# 05_MSM8916_CONTROL.net
KiCad netlist of a schematic drawn in Altium Designer
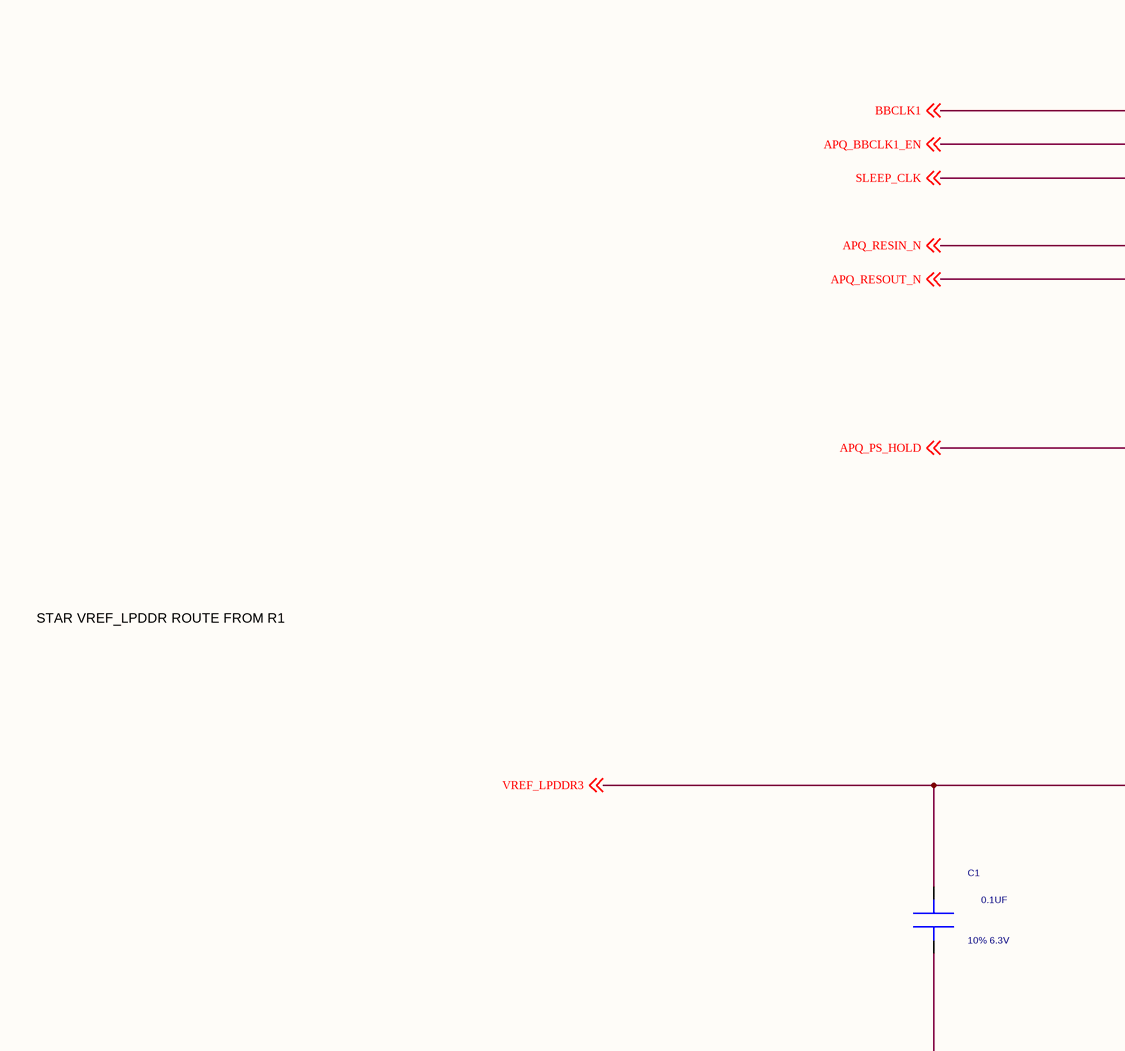
[diagram p0: 05 MSM8916_CONTROL.SchDoc, top left]
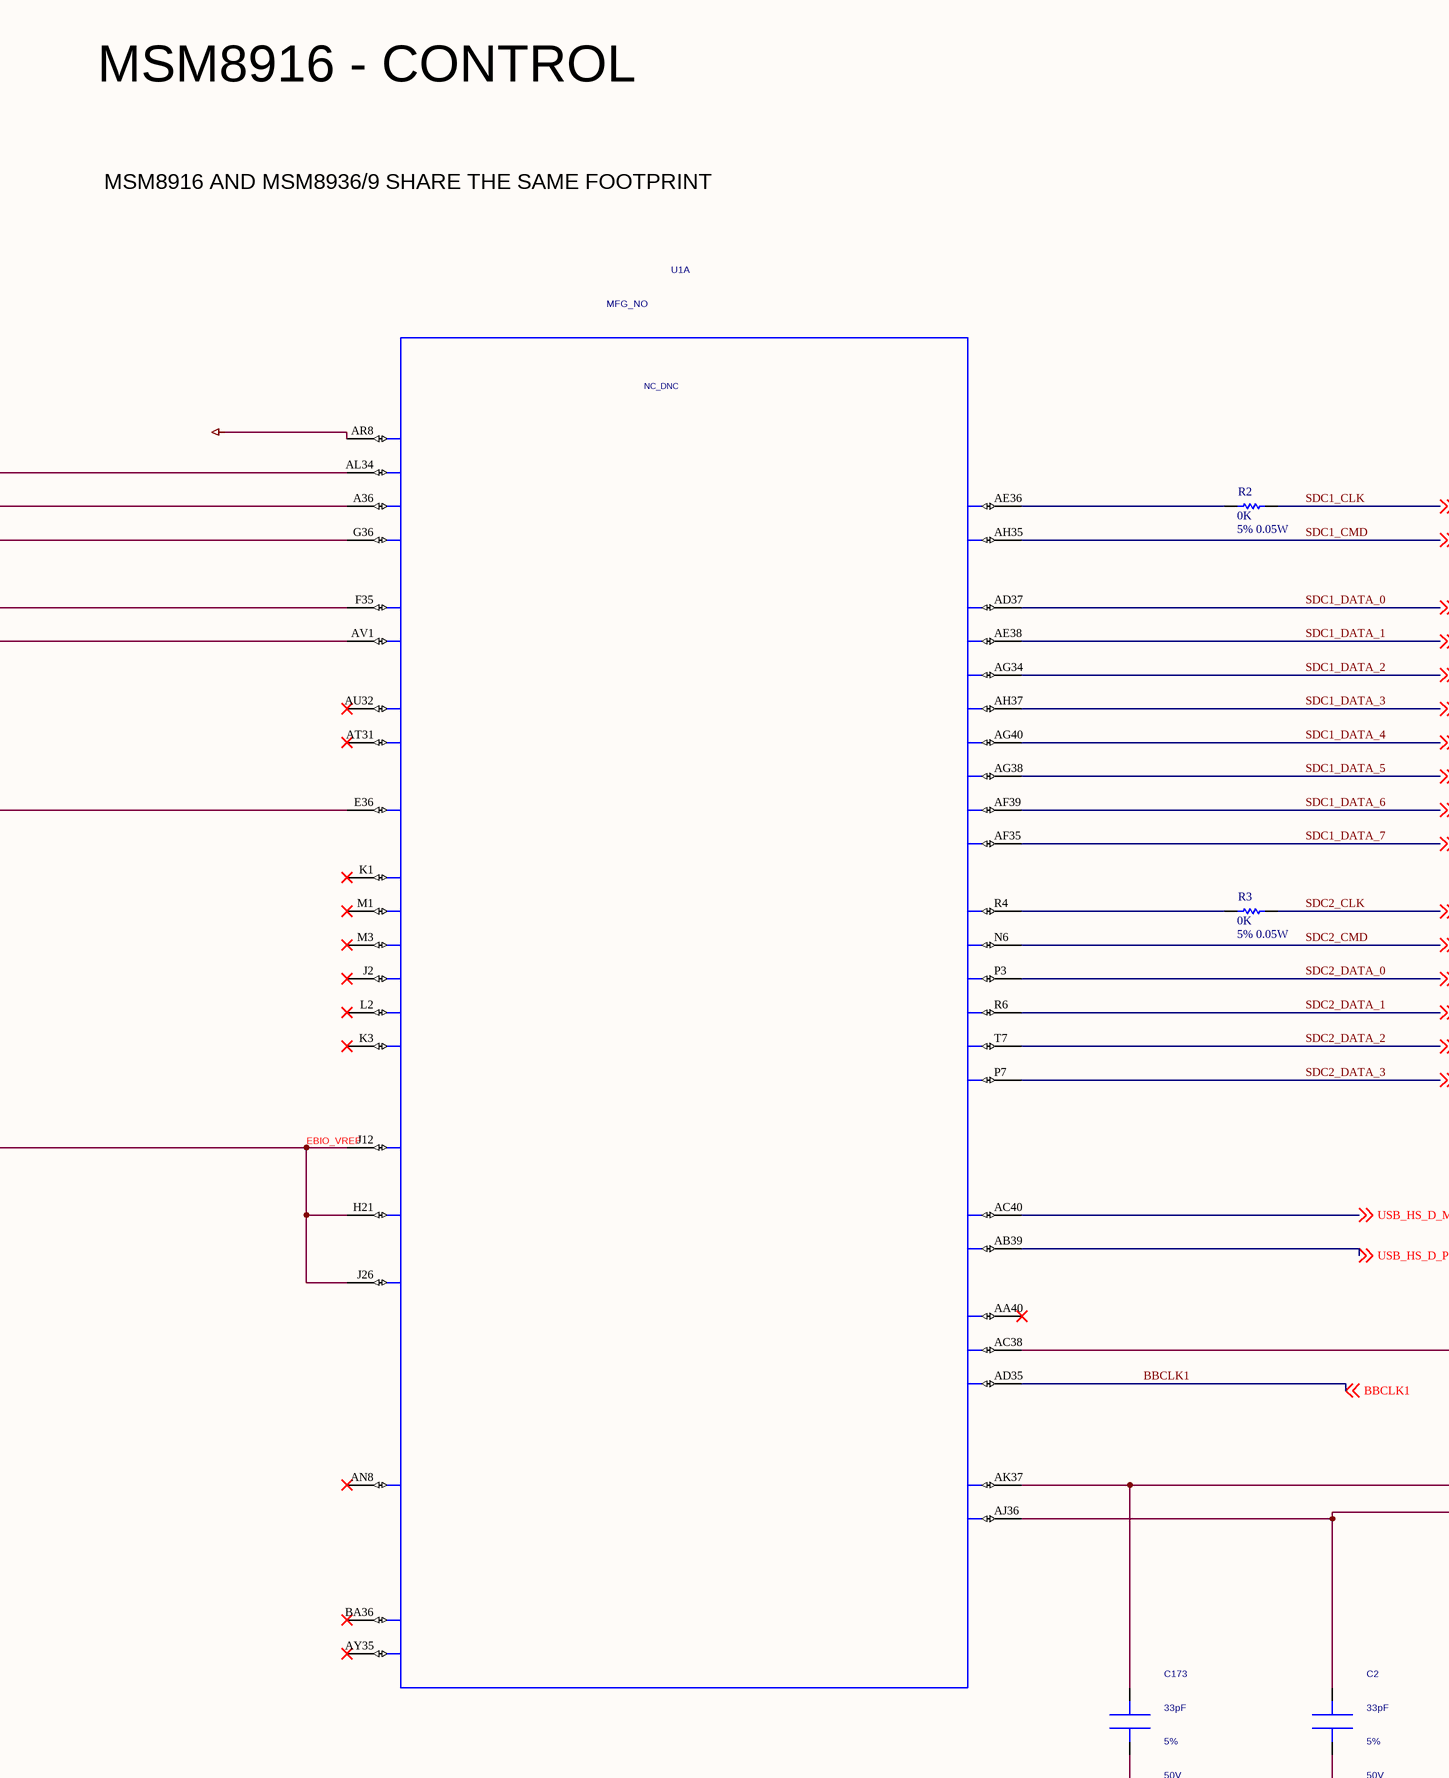
[diagram p1: 05 MSM8916_CONTROL.SchDoc, top middle]
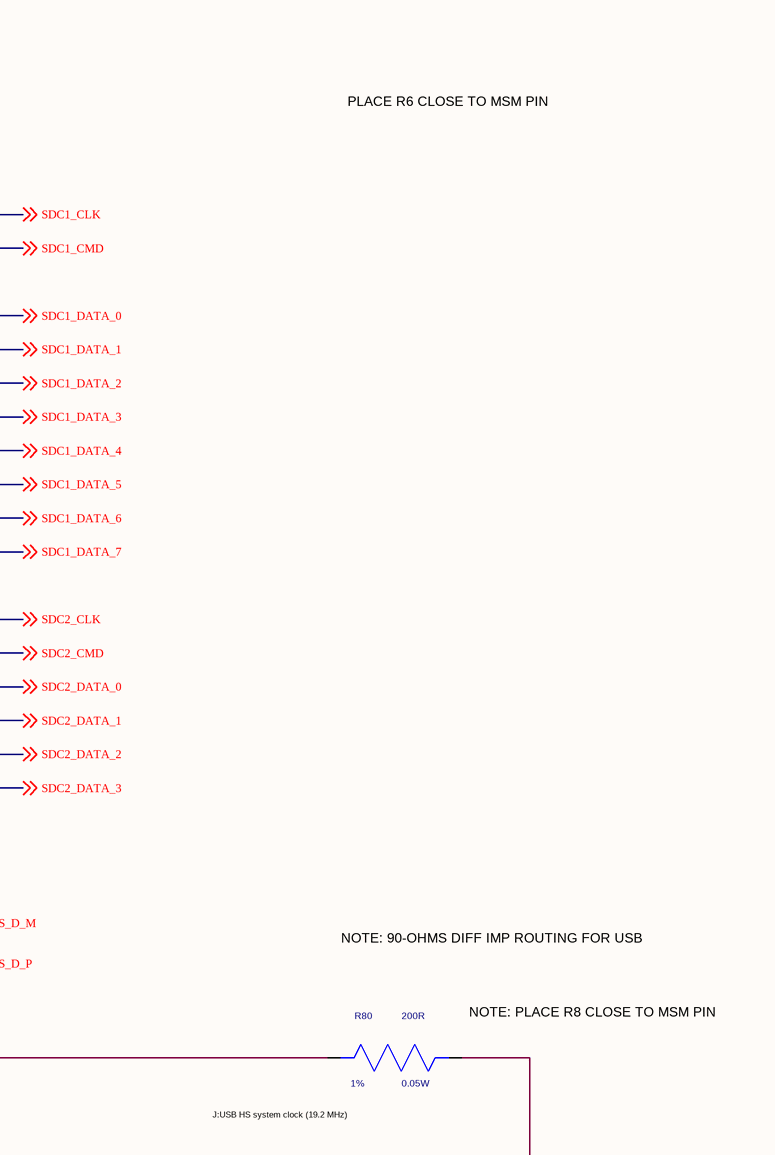
[diagram p2: 05 MSM8916_CONTROL.SchDoc, top right]
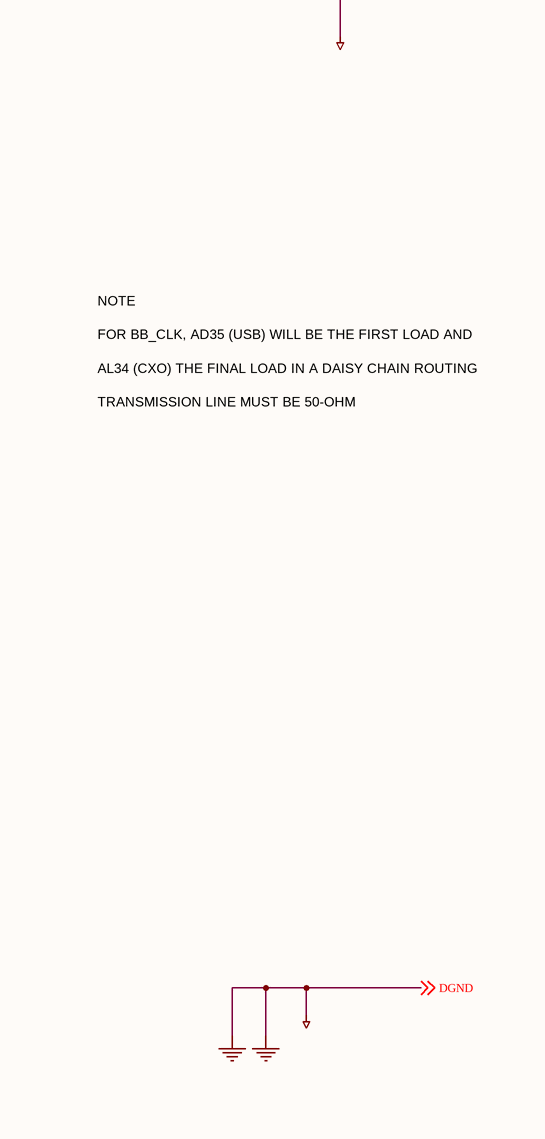
[diagram p3: 05 MSM8916_CONTROL.SchDoc, bottom left]
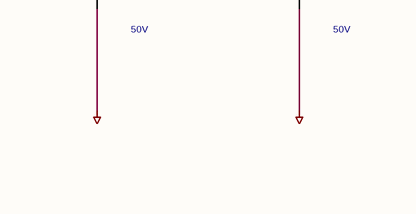
[diagram p4: 05 MSM8916_CONTROL.SchDoc, bottom middle]
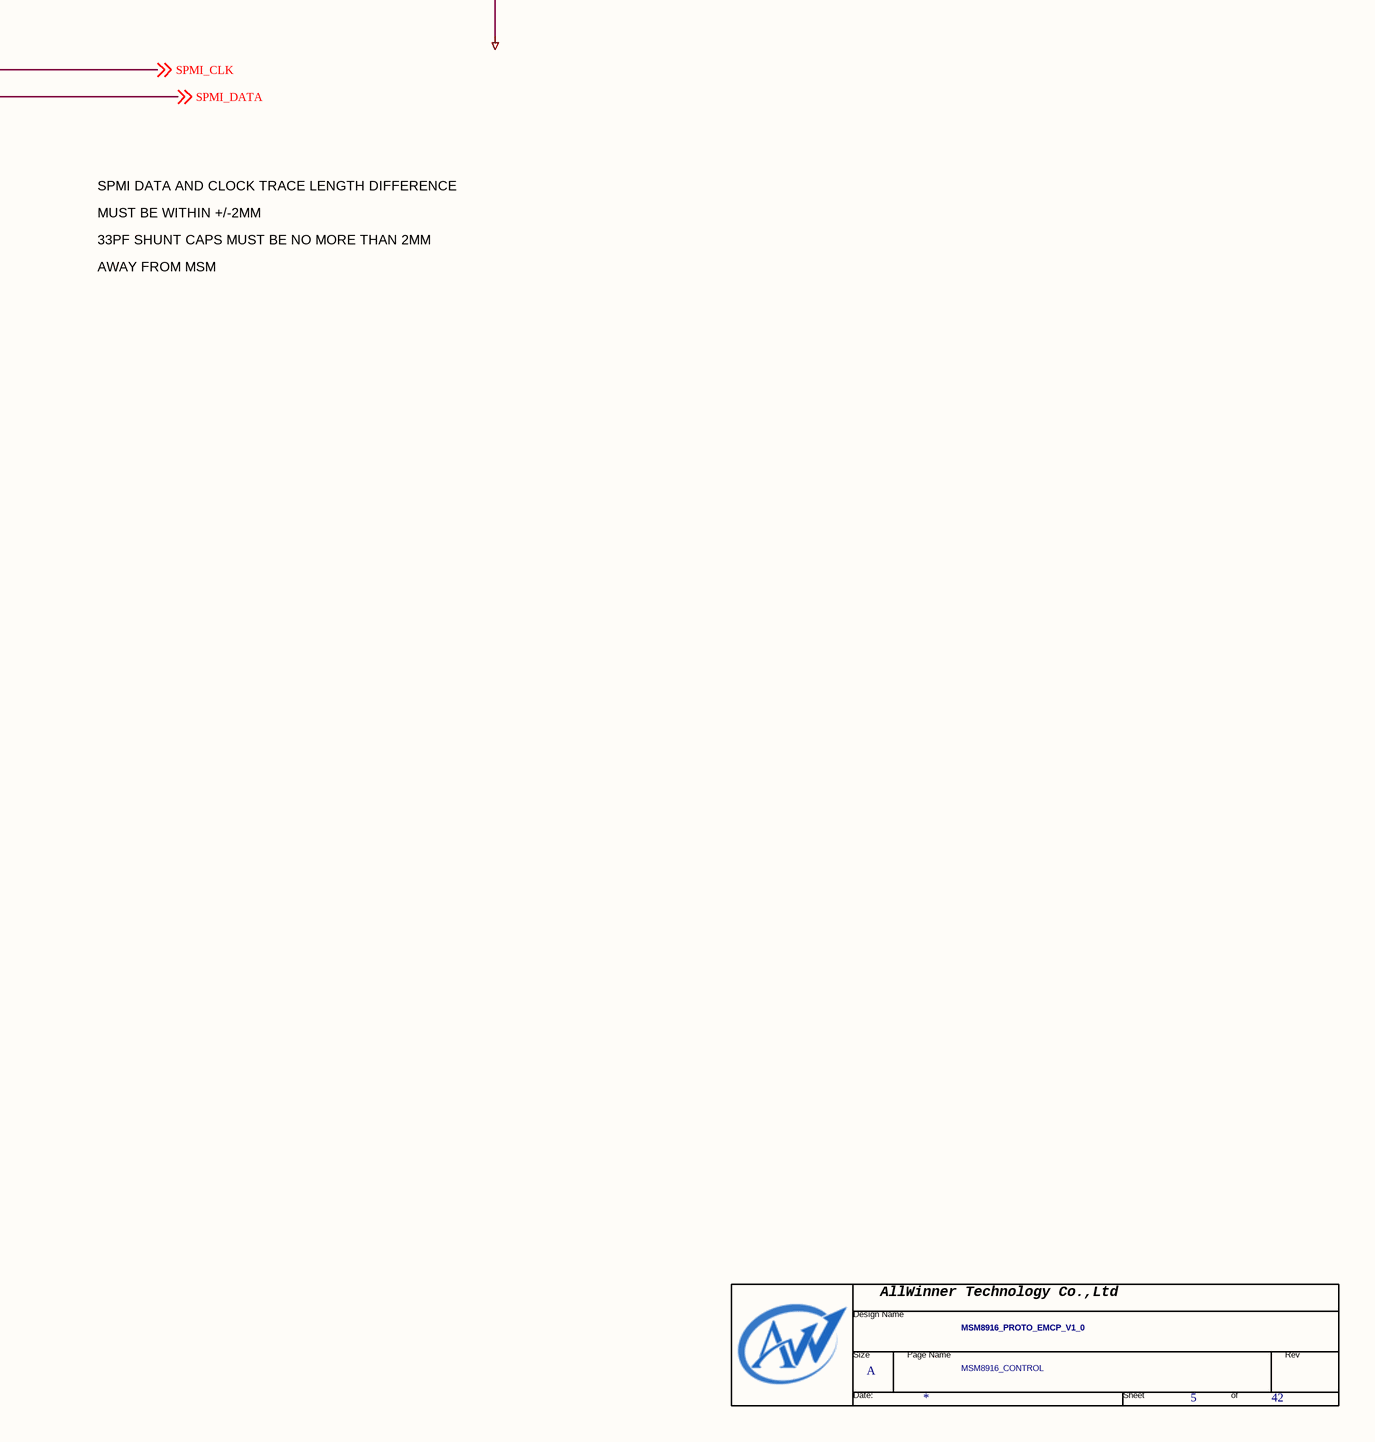
[diagram p5: 05 MSM8916_CONTROL.SchDoc, bottom right]

(export (version "E")
  (design (tool "Eeschema 10.0.6"))
  (components
    (comp (ref "*")
      (value "TitleBlock0-AW")
      (fields
        (field (name "PAGE COUNT") "42")
        (field (name "PAGE NUMBER") "5")
        (field (name "PAGE SIZE") "A")
        (field (name "TITLE") "MSM8916_PROTO_EMCP_V1_0")
        (field (name "DOC") "MSM8916_CONTROL")
      )
      (libsource (lib "*") (part "TitleBlock0-AW"))
    )
    (comp (ref "C1")
      (value "0.1UF")
      (fields (field (name "TOLERANCE") "10% 6.3V") (field (name "PART_NUMBER") "MCN_NO"))
      (libsource (lib "MSM8916_DRAM_PMIC_REF_Library") (part "CAP"))
    )
    (comp (ref "C2")
      (value "33pF")
      (fields
        (field (name "VOLT") "50V")
        (field (name "TOLERANCE") "5%")
        (field (name "PART_NUMBER") "MCN_NO")
      )
      (libsource (lib "MSM8916_DRAM_PMIC_REF_Library") (part "CAP"))
    )
    (comp (ref "C173")
      (value "33pF")
      (fields
        (field (name "VOLT") "50V")
        (field (name "TOLERANCE") "5%")
        (field (name "PART_NUMBER") "MCN_NO")
      )
      (libsource (lib "MSM8916_DRAM_PMIC_REF_Library") (part "CAP"))
    )
    (comp (ref "R2")
      (value "0K")
      (footprint "AXIAL-0.3")
      (description "Resistor")
      (fields (field (name "ALTIUM_VALUE") "5% 0.05W") (field (name "PUBLISHER") "Altium Limited"))
      (libsource (lib "Miscellaneous Devices") (part "Res1"))
    )
    (comp (ref "R3")
      (value "0K")
      (footprint "AXIAL-0.3")
      (description "Resistor")
      (fields (field (name "ALTIUM_VALUE") "5% 0.05W") (field (name "PUBLISHER") "Altium Limited"))
      (libsource (lib "Miscellaneous Devices") (part "Res1"))
    )
    (comp (ref "R80")
      (value "200R")
      (fields
        (field (name "TOLERANCE") "1%")
        (field (name "POWER") "0.05W")
        (field (name "PART_NUMBER") "MCN_NO")
      )
      (libsource (lib "MSM8916_DRAM_PMIC_REF_Library") (part "RESISTOR_Dup3"))
    )
    (comp (ref "U1")
      (value "ASIC_MSM8936_760PIN")
      (footprint "MSM-8916-0-760NSP-TR-00-0")
      (fields
        (field (name "SYMNAME") "NC_DNC")
        (field (name "PART_NUMBER") "MCN_NO")
        (field (name "PART_ID") "MFG_NO")
      )
      (libsource (lib "MSM8916_DRAM_PMIC_REF_Library") (part "ASIC_MSM8936_760PIN"))
    )
  )
  (nets
    (net (code "1") (name "APQ_BBCLK1_EN") (class "Default")
      (node (ref "U1") (pin "A36") (pinfunction "CXO_EN_A36") (pintype "bidirectional"))
    )
    (net (code "2") (name "APQ_PS_HOLD") (class "Default")
      (node (ref "U1") (pin "E36") (pinfunction "PS_HOLD_E36") (pintype "bidirectional"))
    )
    (net (code "3") (name "APQ_RESIN_N") (class "Default")
      (node (ref "U1") (pin "F35") (pinfunction "RESIN*_F35") (pintype "bidirectional"))
    )
    (net (code "4") (name "APQ_RESOUT_N") (class "Default")
      (node (ref "U1") (pin "AV1") (pinfunction "RESOUT*_AV1") (pintype "bidirectional"))
    )
    (net (code "5") (name "BBCLK1") (class "Default")
      (node (ref "U1") (pin "AD35") (pinfunction "USB2_HS_SYSCLOCK_AD35") (pintype "bidirectional"))
      (node (ref "U1") (pin "AL34") (pinfunction "CXO_AL34") (pintype "bidirectional"))
    )
    (net (code "6") (name "DGND") (class "Default")
      (node (ref "C1") (pin "2") (pinfunction "NEG_2") (pintype "bidirectional"))
      (node (ref "C173") (pin "2") (pinfunction "NEG_2") (pintype "bidirectional"))
      (node (ref "C2") (pin "2") (pinfunction "NEG_2") (pintype "bidirectional"))
      (node (ref "R80") (pin "2") (pinfunction "NEG_2") (pintype "bidirectional"))
      (node (ref "U1") (pin "AR8") (pinfunction "WCSS_XO_AR8") (pintype "bidirectional"))
    )
    (net (code "7") (name "Net-(R80-POS)") (class "Default")
      (node (ref "R80") (pin "1") (pinfunction "POS_1") (pintype "bidirectional"))
      (node (ref "U1") (pin "AC38") (pinfunction "USB2_HS_TXRTUNE_AC38") (pintype "bidirectional"))
    )
    (net (code "8") (name "Net-(U1A-SDC1_CLK)") (class "Default")
      (node (ref "R2") (pin "1") (pinfunction "1_1") (pintype "passive"))
      (node (ref "U1") (pin "AE36") (pinfunction "SDC1_CLK_AE36") (pintype "bidirectional"))
    )
    (net (code "9") (name "Net-(U1A-SDC2_CLK)") (class "Default")
      (node (ref "R3") (pin "1") (pinfunction "1_1") (pintype "passive"))
      (node (ref "U1") (pin "R4") (pinfunction "SDC2_CLK_R4") (pintype "bidirectional"))
    )
    (net (code "10") (name "SDC1_CLK") (class "Default")
      (node (ref "R2") (pin "2") (pinfunction "2_2") (pintype "passive"))
    )
    (net (code "11") (name "SDC1_CMD") (class "Default")
      (node (ref "U1") (pin "AH35") (pinfunction "SDC1_CMD_AH35") (pintype "bidirectional"))
    )
    (net (code "12") (name "SDC1_DATA_0") (class "Default")
      (node (ref "U1") (pin "AD37") (pinfunction "SDC1_DATA_0_AD37") (pintype "bidirectional"))
    )
    (net (code "13") (name "SDC1_DATA_1") (class "Default")
      (node (ref "U1") (pin "AE38") (pinfunction "SDC1_DATA_1_AE38") (pintype "bidirectional"))
    )
    (net (code "14") (name "SDC1_DATA_2") (class "Default")
      (node (ref "U1") (pin "AG34") (pinfunction "SDC1_DATA_2_AG34") (pintype "bidirectional"))
    )
    (net (code "15") (name "SDC1_DATA_3") (class "Default")
      (node (ref "U1") (pin "AH37") (pinfunction "SDC1_DATA_3_AH37") (pintype "bidirectional"))
    )
    (net (code "16") (name "SDC1_DATA_4") (class "Default")
      (node (ref "U1") (pin "AG40") (pinfunction "SDC1_DATA_4_AG40") (pintype "bidirectional"))
    )
    (net (code "17") (name "SDC1_DATA_5") (class "Default")
      (node (ref "U1") (pin "AG38") (pinfunction "SDC1_DATA_5_AG38") (pintype "bidirectional"))
    )
    (net (code "18") (name "SDC1_DATA_6") (class "Default")
      (node (ref "U1") (pin "AF39") (pinfunction "SDC1_DATA_6_AF39") (pintype "bidirectional"))
    )
    (net (code "19") (name "SDC1_DATA_7") (class "Default")
      (node (ref "U1") (pin "AF35") (pinfunction "SDC1_DATA_7_AF35") (pintype "bidirectional"))
    )
    (net (code "20") (name "SDC2_CLK") (class "Default")
      (node (ref "R3") (pin "2") (pinfunction "2_2") (pintype "passive"))
    )
    (net (code "21") (name "SDC2_CMD") (class "Default")
      (node (ref "U1") (pin "N6") (pinfunction "SDC2_CMD_N6") (pintype "bidirectional"))
    )
    (net (code "22") (name "SDC2_DATA_0") (class "Default")
      (node (ref "U1") (pin "P3") (pinfunction "SDC2_DATA_0_P3") (pintype "bidirectional"))
    )
    (net (code "23") (name "SDC2_DATA_1") (class "Default")
      (node (ref "U1") (pin "R6") (pinfunction "SDC2_DATA_1_R6") (pintype "bidirectional"))
    )
    (net (code "24") (name "SDC2_DATA_2") (class "Default")
      (node (ref "U1") (pin "T7") (pinfunction "SDC2_DATA_2_T7") (pintype "bidirectional"))
    )
    (net (code "25") (name "SDC2_DATA_3") (class "Default")
      (node (ref "U1") (pin "P7") (pinfunction "SDC2_DATA_3_P7") (pintype "bidirectional"))
    )
    (net (code "26") (name "SLEEP_CLK") (class "Default")
      (node (ref "U1") (pin "G36") (pinfunction "SLEEP_CLK_G36") (pintype "bidirectional"))
    )
    (net (code "27") (name "SPMI_CLK") (class "Default")
      (node (ref "C173") (pin "1") (pinfunction "POS_1") (pintype "bidirectional"))
      (node (ref "U1") (pin "AK37") (pinfunction "PMIC_SPMI_CLK_AK37") (pintype "bidirectional"))
    )
    (net (code "28") (name "SPMI_DATA") (class "Default")
      (node (ref "C2") (pin "1") (pinfunction "POS_1") (pintype "bidirectional"))
      (node (ref "U1") (pin "AJ36") (pinfunction "PMIC_SPMI_DATA_AJ36") (pintype "bidirectional"))
    )
    (net (code "29") (name "USB_HS_D_M") (class "Default")
      (node (ref "U1") (pin "AC40") (pinfunction "USB2_HS_DM_AC40") (pintype "bidirectional"))
    )
    (net (code "30") (name "USB_HS_D_P") (class "Default")
      (node (ref "U1") (pin "AB39") (pinfunction "USB2_HS_DP_AB39") (pintype "bidirectional"))
    )
    (net (code "31") (name "VREF_LPDDR3") (class "Default")
      (node (ref "C1") (pin "1") (pinfunction "POS_1") (pintype "bidirectional"))
      (node (ref "U1") (pin "H21") (pinfunction "VREF_EBI0_D0_D2_H21") (pintype "bidirectional"))
      (node (ref "U1") (pin "J12") (pinfunction "VREF_EBI0_CA_J12") (pintype "bidirectional"))
      (node (ref "U1") (pin "J26") (pinfunction "VREF_EBI0_D1_D3_J26") (pintype "bidirectional"))
    )
    (net (code "32") (name "unconnected-(U1A-ATEST0-PadBA36)") (class "Default")
      (node (ref "U1") (pin "BA36") (pinfunction "ATEST0_BA36") (pintype "bidirectional+no_connect"))
    )
    (net (code "33") (name "unconnected-(U1A-ATEST1-PadAY35)") (class "Default")
      (node (ref "U1") (pin "AY35") (pinfunction "ATEST1_AY35") (pintype "bidirectional+no_connect"))
    )
    (net (code "34") (name "unconnected-(U1A-MODE_0-PadAU32)") (class "Default")
      (node (ref "U1") (pin "AU32") (pinfunction "MODE_0_AU32") (pintype "bidirectional+no_connect"))
    )
    (net (code "35") (name "unconnected-(U1A-MODE_1-PadAT31)") (class "Default")
      (node (ref "U1") (pin "AT31") (pinfunction "MODE_1_AT31") (pintype "bidirectional+no_connect"))
    )
    (net (code "36") (name "unconnected-(U1A-PLL_TEST_SE-PadAN8)") (class "Default")
      (node (ref "U1") (pin "AN8") (pinfunction "PLL_TEST_SE_AN8") (pintype "bidirectional+no_connect"))
    )
    (net (code "37") (name "unconnected-(U1A-SRST*-PadK1)") (class "Default")
      (node (ref "U1") (pin "K1") (pinfunction "SRST*_K1") (pintype "bidirectional+no_connect"))
    )
    (net (code "38") (name "unconnected-(U1A-TCK-PadM1)") (class "Default")
      (node (ref "U1") (pin "M1") (pinfunction "TCK_M1") (pintype "bidirectional+no_connect"))
    )
    (net (code "39") (name "unconnected-(U1A-TDI-PadM3)") (class "Default")
      (node (ref "U1") (pin "M3") (pinfunction "TDI_M3") (pintype "bidirectional+no_connect"))
    )
    (net (code "40") (name "unconnected-(U1A-TDO-PadJ2)") (class "Default")
      (node (ref "U1") (pin "J2") (pinfunction "TDO_J2") (pintype "bidirectional+no_connect"))
    )
    (net (code "41") (name "unconnected-(U1A-TMS-PadL2)") (class "Default")
      (node (ref "U1") (pin "L2") (pinfunction "TMS_L2") (pintype "bidirectional+no_connect"))
    )
    (net (code "42") (name "unconnected-(U1A-TRST*-PadK3)") (class "Default")
      (node (ref "U1") (pin "K3") (pinfunction "TRST*_K3") (pintype "bidirectional+no_connect"))
    )
    (net (code "43") (name "unconnected-(U1A-USB2_HS_ID-PadAA40)") (class "Default")
      (node (ref "U1") (pin "AA40") (pinfunction "USB2_HS_ID_AA40") (pintype "bidirectional+no_connect"))
    )
  )
)
